# JLink-OB-Wiki.net
KiCad netlist of a schematic drawn in Altium Designer
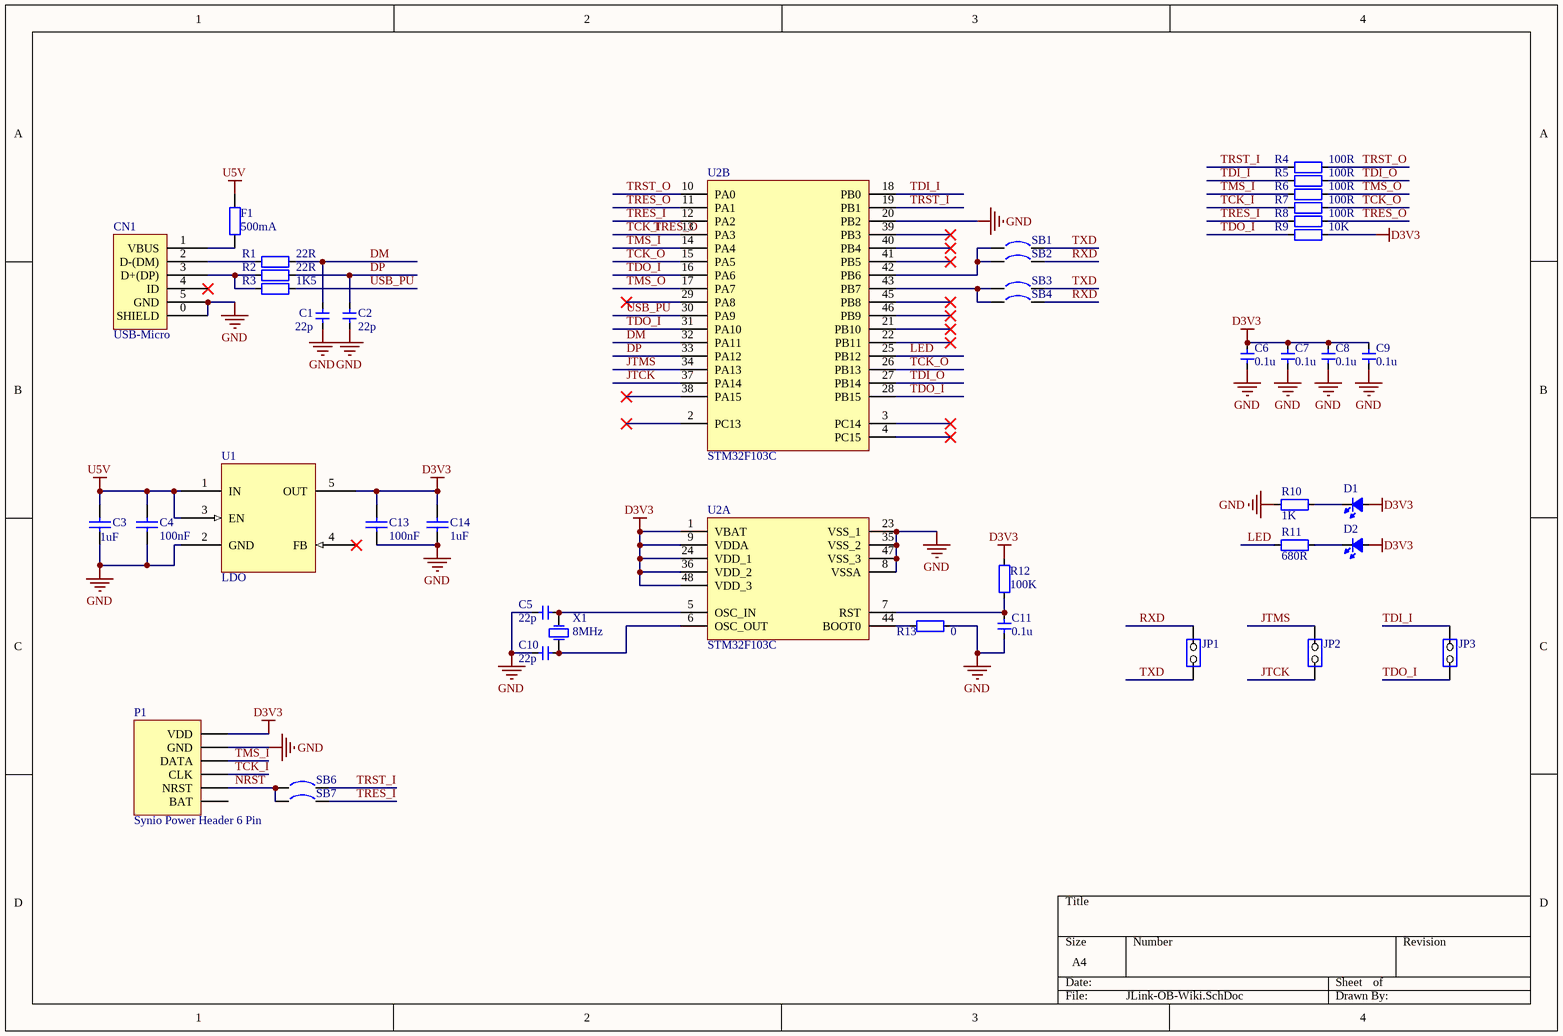
[diagram p0: JLink-OB-Wiki.SchDoc]

(export (version "E")
  (design (tool "Eeschema 10.0.6"))
  (components
    (comp (ref "C1")
      (value "22p")
      (footprint "0603C")
      (description "Capacitor")
      (fields (field (name "Comment") "Cap_0603"))
      (libsource (lib "altium-import") (part "root_1_Cap_0603_"))
    )
    (comp (ref "C2")
      (value "22p")
      (footprint "0603C")
      (description "Capacitor")
      (fields (field (name "Comment") "Cap_0603"))
      (libsource (lib "SCH_Passive") (part "Cap_0603"))
    )
    (comp (ref "C3")
      (value "1uF")
      (footprint "0603C")
      (description "0603  X5R 1礔")
      (fields (field (name "TOLERANCE") "10%"))
      (libsource (lib "MB963_1") (part "CAP SMD 0603  X5R 1礔 25V 10%"))
    )
    (comp (ref "C4")
      (value "100nF")
      (footprint "0603C")
      (description "Capacitor 0402 / 0603 / 0805")
      (libsource (lib "MCD_TOOLS") (part "Capacitor_ST"))
    )
    (comp (ref "C5")
      (value "22p")
      (footprint "0603C")
      (description "Capacitor")
      (fields (field (name "Comment") "Cap_0603"))
      (libsource (lib "SCH_Passive") (part "Cap_0603"))
    )
    (comp (ref "C6")
      (value "0.1u")
      (footprint "0603C")
      (description "Capacitor")
      (fields (field (name "Comment") "Cap_0603"))
      (libsource (lib "SCH_Passive") (part "Cap_0603"))
    )
    (comp (ref "C7")
      (value "0.1u")
      (footprint "0603C")
      (description "Capacitor")
      (fields (field (name "Comment") "Cap_0603"))
      (libsource (lib "SCH_Passive") (part "Cap_0603"))
    )
    (comp (ref "C8")
      (value "0.1u")
      (footprint "0603C")
      (description "Capacitor")
      (fields (field (name "Comment") "Cap_0603"))
      (libsource (lib "SCH_Passive") (part "Cap_0603"))
    )
    (comp (ref "C9")
      (value "0.1u")
      (footprint "0603C")
      (description "Capacitor")
      (fields (field (name "Comment") "Cap_0603"))
      (libsource (lib "SCH_Passive") (part "Cap_0603"))
    )
    (comp (ref "C10")
      (value "22p")
      (footprint "0603C")
      (description "Capacitor")
      (fields (field (name "Comment") "Cap_0603"))
      (libsource (lib "SCH_Passive") (part "Cap_0603"))
    )
    (comp (ref "C11")
      (value "0.1u")
      (footprint "0603C")
      (description "Capacitor")
      (fields (field (name "Comment") "Cap_0603"))
      (libsource (lib "SCH_Passive") (part "Cap_0603"))
    )
    (comp (ref "C13")
      (value "100nF")
      (footprint "0603C")
      (description "Capacitor 0402 / 0603 / 0805")
      (libsource (lib "MCD_TOOLS") (part "Capacitor_ST"))
    )
    (comp (ref "C14")
      (value "1uF")
      (footprint "0603C")
      (description "0603  X5R 1礔")
      (fields (field (name "TOLERANCE") "10%"))
      (libsource (lib "MB963_1") (part "CAP SMD 0603  X5R 1礔 25V 10%"))
    )
    (comp (ref "CN1")
      (value "USB-Micro")
      (footprint "USB_MICRO_5S_B")
      (libsource (lib "USB") (part "USB-Micro"))
    )
    (comp (ref "D1")
      (value "LED_0603")
      (footprint "LED-0603")
      (description "LED")
      (libsource (lib "SCH_Active") (part "LED_0603"))
    )
    (comp (ref "D2")
      (value "LED_0603")
      (footprint "LED-0603")
      (description "LED")
      (libsource (lib "SCH_Active") (part "LED_0603"))
    )
    (comp (ref "F1")
      (value "500mA")
      (footprint "0805M")
      (description "Resistor")
      (fields (field (name "PUBLISHER") "Altium Limited"))
      (libsource (lib "Misc") (part "Res"))
    )
    (comp (ref "JP1") (value "JP2") (footprint "HDR1X2/2.54mm") (libsource (lib "Connector") (part "JP2")))
    (comp (ref "JP2") (value "JP2") (footprint "HDR1X2/2.54mm") (libsource (lib "Connector") (part "JP2")))
    (comp (ref "JP3") (value "JP2") (footprint "HDR1X2/2.54mm") (libsource (lib "Connector") (part "JP2")))
    (comp (ref "P1")
      (value "Synio Power Header 6 Pin")
      (footprint "HDR1X6/2.54MM")
      (libsource (lib "Connector") (part "Synio Power Header 6 Pin"))
    )
    (comp (ref "R1")
      (value "22R")
      (footprint "0603R")
      (description "Resistor")
      (fields (field (name "Comment") "Res_0603"))
      (libsource (lib "SCH_Passive") (part "Res_0603"))
    )
    (comp (ref "R2")
      (value "22R")
      (footprint "0603R")
      (description "Resistor")
      (fields (field (name "Comment") "Res_0603"))
      (libsource (lib "SCH_Passive") (part "Res_0603"))
    )
    (comp (ref "R3")
      (value "1K5")
      (footprint "0603R")
      (description "Resistor")
      (fields (field (name "Comment") "Res_0603"))
      (libsource (lib "SCH_Passive") (part "Res_0603"))
    )
    (comp (ref "R4")
      (value "100R")
      (footprint "0603R")
      (description "Resistor")
      (fields (field (name "Comment") "Res_0603"))
      (libsource (lib "altium-import") (part "root_0_Res_0603_"))
    )
    (comp (ref "R5")
      (value "100R")
      (footprint "0603R")
      (description "Resistor")
      (fields (field (name "Comment") "Res_0603"))
      (libsource (lib "SCH_Passive") (part "Res_0603"))
    )
    (comp (ref "R6")
      (value "100R")
      (footprint "0603R")
      (description "Resistor")
      (fields (field (name "Comment") "Res_0603"))
      (libsource (lib "SCH_Passive") (part "Res_0603"))
    )
    (comp (ref "R7")
      (value "100R")
      (footprint "0603R")
      (description "Resistor")
      (fields (field (name "Comment") "Res_0603"))
      (libsource (lib "SCH_Passive") (part "Res_0603"))
    )
    (comp (ref "R8")
      (value "100R")
      (footprint "0603R")
      (description "Resistor")
      (fields (field (name "Comment") "Res_0603"))
      (libsource (lib "SCH_Passive") (part "Res_0603"))
    )
    (comp (ref "R9")
      (value "10K")
      (footprint "0603R")
      (description "Resistor")
      (fields (field (name "Comment") "Res_0603"))
      (libsource (lib "SCH_Passive") (part "Res_0603"))
    )
    (comp (ref "R10")
      (value "1K")
      (footprint "0603R")
      (description "Resistor")
      (fields (field (name "Comment") "Res_0603"))
      (libsource (lib "SCH_Passive") (part "Res_0603"))
    )
    (comp (ref "R11")
      (value "680R")
      (footprint "0603R")
      (description "Resistor")
      (fields (field (name "Comment") "Res_0603"))
      (libsource (lib "SCH_Passive") (part "Res_0603"))
    )
    (comp (ref "R12")
      (value "100K")
      (footprint "0603R")
      (description "Resistor")
      (fields (field (name "Comment") "Res_0603"))
      (libsource (lib "") (part "Res_0603_2"))
    )
    (comp (ref "R13")
      (value "0")
      (footprint "0603R")
      (description "Resistor")
      (fields (field (name "Comment") "Res_0603"))
      (libsource (lib "") (part "Res_0603_1"))
    )
    (comp (ref "SB1")
      (value "Circuit Breaker")
      (footprint "JP2_SMD")
      (fields (field (name "PUBLISHER") "Altium Limited"))
      (libsource (lib "Misc") (part "Circuit Breaker"))
    )
    (comp (ref "SB2")
      (value "Circuit Breaker")
      (footprint "JP2_SMD")
      (fields (field (name "PUBLISHER") "Altium Limited"))
      (libsource (lib "Misc") (part "Circuit Breaker"))
    )
    (comp (ref "SB3")
      (value "Circuit Breaker")
      (footprint "JP2_SMD")
      (fields (field (name "PUBLISHER") "Altium Limited"))
      (libsource (lib "Misc") (part "Circuit Breaker"))
    )
    (comp (ref "SB4")
      (value "Circuit Breaker")
      (footprint "JP2_SMD")
      (fields (field (name "PUBLISHER") "Altium Limited"))
      (libsource (lib "Misc") (part "Circuit Breaker"))
    )
    (comp (ref "SB6")
      (value "Circuit Breaker")
      (footprint "JP2_SMD")
      (fields (field (name "PUBLISHER") "Altium Limited"))
      (libsource (lib "Misc") (part "Circuit Breaker"))
    )
    (comp (ref "SB7")
      (value "Circuit Breaker")
      (footprint "JP2_SMD")
      (fields (field (name "PUBLISHER") "Altium Limited"))
      (libsource (lib "Misc") (part "Circuit Breaker"))
    )
    (comp (ref "U1")
      (value "LDO")
      (footprint "SOT23-5")
      (description "General LDO SOT23-5")
      (libsource (lib "Power") (part "LDO-SOT23-5"))
    )
    (comp (ref "U2")
      (value "STM32F103C")
      (footprint "LQFP48_N")
      (description "MCU")
      (libsource (lib "SCH_IC") (part "STM32F103C"))
    )
    (comp (ref "X1")
      (value "8MHz")
      (footprint "XTAL")
      (description "Crystal Oscillator")
      (fields (field (name "Comment") "XTAL_5032_2P"))
      (libsource (lib "SCH_Oscillator") (part "XTAL_5032_2P"))
    )
  )
  (nets
    (net (code "1") (name "/DM") (class "Default")
      (node (ref "C1") (pin "2") (pinfunction "2_2") (pintype "passive"))
      (node (ref "R1") (pin "2") (pinfunction "2_2") (pintype "passive"))
      (node (ref "U2") (pin "32") (pinfunction "PA11_32") (pintype "passive"))
    )
    (net (code "2") (name "/DP") (class "Default")
      (node (ref "C2") (pin "2") (pinfunction "2_2") (pintype "passive"))
      (node (ref "R2") (pin "2") (pinfunction "2_2") (pintype "passive"))
      (node (ref "U2") (pin "33") (pinfunction "PA12_33") (pintype "passive"))
    )
    (net (code "3") (name "/JTCK") (class "Default")
      (node (ref "JP2") (pin "1") (pinfunction "COMMON_1") (pintype "passive"))
      (node (ref "U2") (pin "37") (pinfunction "PA14_37") (pintype "passive"))
    )
    (net (code "4") (name "/JTMS") (class "Default")
      (node (ref "JP2") (pin "2") (pinfunction "NO_2") (pintype "passive"))
      (node (ref "U2") (pin "34") (pinfunction "PA13_34") (pintype "passive"))
    )
    (net (code "5") (name "/LED") (class "Default")
      (node (ref "R11") (pin "1") (pinfunction "1_1") (pintype "passive"))
      (node (ref "U2") (pin "25") (pinfunction "PB12_25") (pintype "passive"))
    )
    (net (code "6") (name "/NRST") (class "Default")
      (node (ref "P1") (pin "5") (pinfunction "NRST_5") (pintype "passive"))
      (node (ref "SB6") (pin "1") (pinfunction "1_1") (pintype "passive"))
      (node (ref "SB7") (pin "1") (pinfunction "1_1") (pintype "passive"))
    )
    (net (code "7") (name "/RXD") (class "Default")
      (node (ref "JP1") (pin "2") (pinfunction "NO_2") (pintype "passive"))
      (node (ref "SB2") (pin "2") (pinfunction "2_2") (pintype "passive"))
      (node (ref "SB4") (pin "2") (pinfunction "2_2") (pintype "passive"))
    )
    (net (code "8") (name "/TCK_I") (class "Default")
      (node (ref "P1") (pin "4") (pinfunction "CLK_4") (pintype "passive"))
      (node (ref "R7") (pin "1") (pinfunction "1_1") (pintype "passive"))
      (node (ref "R8") (pin "2") (pinfunction "2_2") (pintype "passive"))
      (node (ref "U2") (pin "11") (pinfunction "PA1_11") (pintype "passive"))
      (node (ref "U2") (pin "13") (pinfunction "PA3_13") (pintype "passive"))
    )
    (net (code "9") (name "/TCK_O") (class "Default")
      (node (ref "R7") (pin "2") (pinfunction "2_2") (pintype "passive"))
      (node (ref "U2") (pin "15") (pinfunction "PA5_15") (pintype "passive"))
      (node (ref "U2") (pin "26") (pinfunction "PB13_26") (pintype "passive"))
    )
    (net (code "10") (name "/TDI_I") (class "Default")
      (node (ref "JP3") (pin "2") (pinfunction "NO_2") (pintype "passive"))
      (node (ref "R5") (pin "1") (pinfunction "1_1") (pintype "passive"))
      (node (ref "U2") (pin "18") (pinfunction "PB0_18") (pintype "passive"))
    )
    (net (code "11") (name "/TDI_O") (class "Default")
      (node (ref "R5") (pin "2") (pinfunction "2_2") (pintype "passive"))
      (node (ref "U2") (pin "27") (pinfunction "PB14_27") (pintype "passive"))
    )
    (net (code "12") (name "/TDO_I") (class "Default")
      (node (ref "JP3") (pin "1") (pinfunction "COMMON_1") (pintype "passive"))
      (node (ref "R9") (pin "1") (pinfunction "1_1") (pintype "passive"))
      (node (ref "U2") (pin "16") (pinfunction "PA6_16") (pintype "passive"))
      (node (ref "U2") (pin "28") (pinfunction "PB15_28") (pintype "passive"))
      (node (ref "U2") (pin "31") (pinfunction "PA10_31") (pintype "passive"))
    )
    (net (code "13") (name "/TMS_I") (class "Default")
      (node (ref "P1") (pin "3") (pinfunction "DATA_3") (pintype "passive"))
      (node (ref "R6") (pin "1") (pinfunction "1_1") (pintype "passive"))
      (node (ref "U2") (pin "14") (pinfunction "PA4_14") (pintype "passive"))
    )
    (net (code "14") (name "/TMS_O") (class "Default")
      (node (ref "R6") (pin "2") (pinfunction "2_2") (pintype "passive"))
      (node (ref "U2") (pin "17") (pinfunction "PA7_17") (pintype "passive"))
    )
    (net (code "15") (name "/TRES_I") (class "Default")
      (node (ref "R8") (pin "1") (pinfunction "1_1") (pintype "passive"))
      (node (ref "SB7") (pin "2") (pinfunction "2_2") (pintype "passive"))
      (node (ref "U2") (pin "12") (pinfunction "PA2_12") (pintype "passive"))
    )
    (net (code "16") (name "/TRST_I") (class "Default")
      (node (ref "R4") (pin "1") (pinfunction "1_1") (pintype "passive"))
      (node (ref "SB6") (pin "2") (pinfunction "2_2") (pintype "passive"))
      (node (ref "U2") (pin "19") (pinfunction "PB1_19") (pintype "passive"))
    )
    (net (code "17") (name "/TRST_O") (class "Default")
      (node (ref "R4") (pin "2") (pinfunction "2_2") (pintype "passive"))
      (node (ref "U2") (pin "10") (pinfunction "PA0_10") (pintype "passive"))
    )
    (net (code "18") (name "/TXD") (class "Default")
      (node (ref "JP1") (pin "1") (pinfunction "COMMON_1") (pintype "passive"))
      (node (ref "SB1") (pin "2") (pinfunction "2_2") (pintype "passive"))
      (node (ref "SB3") (pin "2") (pinfunction "2_2") (pintype "passive"))
    )
    (net (code "19") (name "/USB_PU") (class "Default")
      (node (ref "R3") (pin "2") (pinfunction "2_2") (pintype "passive"))
      (node (ref "U2") (pin "30") (pinfunction "PA9_30") (pintype "passive"))
    )
    (net (code "20") (name "D3V3") (class "Default")
      (node (ref "C13") (pin "2") (pinfunction "2_2") (pintype "passive"))
      (node (ref "C14") (pin "1") (pinfunction "1_1") (pintype "passive"))
      (node (ref "C6") (pin "1") (pinfunction "1_1") (pintype "passive"))
      (node (ref "C7") (pin "1") (pinfunction "1_1") (pintype "passive"))
      (node (ref "C8") (pin "1") (pinfunction "1_1") (pintype "passive"))
      (node (ref "C9") (pin "1") (pinfunction "1_1") (pintype "passive"))
      (node (ref "D1") (pin "1") (pinfunction "A_1") (pintype "passive"))
      (node (ref "D2") (pin "1") (pinfunction "A_1") (pintype "passive"))
      (node (ref "P1") (pin "1") (pinfunction "VDD_1") (pintype "passive"))
      (node (ref "R12") (pin "2") (pinfunction "2_2") (pintype "passive"))
      (node (ref "R9") (pin "2") (pinfunction "2_2") (pintype "passive"))
      (node (ref "U1") (pin "5") (pinfunction "OUT_5") (pintype "power_in"))
      (node (ref "U2") (pin "1") (pinfunction "VBAT_1") (pintype "passive"))
      (node (ref "U2") (pin "24") (pinfunction "VDD_1_24") (pintype "passive"))
      (node (ref "U2") (pin "36") (pinfunction "VDD_2_36") (pintype "passive"))
      (node (ref "U2") (pin "48") (pinfunction "VDD_3_48") (pintype "passive"))
      (node (ref "U2") (pin "9") (pinfunction "VDDA_9") (pintype "passive"))
    )
    (net (code "21") (name "GND") (class "Default")
      (node (ref "C1") (pin "1") (pinfunction "1_1") (pintype "passive"))
      (node (ref "C10") (pin "2") (pinfunction "2_2") (pintype "passive"))
      (node (ref "C11") (pin "2") (pinfunction "2_2") (pintype "passive"))
      (node (ref "C13") (pin "1") (pinfunction "1_1") (pintype "passive"))
      (node (ref "C14") (pin "2") (pinfunction "2_2") (pintype "passive"))
      (node (ref "C2") (pin "1") (pinfunction "1_1") (pintype "passive"))
      (node (ref "C3") (pin "1") (pinfunction "1_1") (pintype "passive"))
      (node (ref "C4") (pin "1") (pinfunction "1_1") (pintype "passive"))
      (node (ref "C5") (pin "2") (pinfunction "2_2") (pintype "passive"))
      (node (ref "C6") (pin "2") (pinfunction "2_2") (pintype "passive"))
      (node (ref "C7") (pin "2") (pinfunction "2_2") (pintype "passive"))
      (node (ref "C8") (pin "2") (pinfunction "2_2") (pintype "passive"))
      (node (ref "C9") (pin "2") (pinfunction "2_2") (pintype "passive"))
      (node (ref "CN1") (pin "0") (pinfunction "SHIELD_0") (pintype "passive"))
      (node (ref "CN1") (pin "5") (pinfunction "GND_5") (pintype "passive"))
      (node (ref "P1") (pin "2") (pinfunction "GND_2") (pintype "passive"))
      (node (ref "R10") (pin "1") (pinfunction "1_1") (pintype "passive"))
      (node (ref "R13") (pin "1") (pinfunction "1_1") (pintype "passive"))
      (node (ref "U1") (pin "2") (pinfunction "GND_2") (pintype "power_in"))
      (node (ref "U2") (pin "20") (pinfunction "PB2_20") (pintype "passive"))
      (node (ref "U2") (pin "23") (pinfunction "VSS_1_23") (pintype "passive"))
      (node (ref "U2") (pin "35") (pinfunction "VSS_2_35") (pintype "passive"))
      (node (ref "U2") (pin "47") (pinfunction "VSS_3_47") (pintype "passive"))
      (node (ref "U2") (pin "8") (pinfunction "VSSA_8") (pintype "passive"))
    )
    (net (code "22") (name "Net-(CN1-D+(DP))") (class "Default")
      (node (ref "CN1") (pin "3") (pinfunction "D+(DP)_3") (pintype "passive"))
      (node (ref "R2") (pin "1") (pinfunction "1_1") (pintype "passive"))
      (node (ref "R3") (pin "1") (pinfunction "1_1") (pintype "passive"))
    )
    (net (code "23") (name "Net-(CN1-D-(DM))") (class "Default")
      (node (ref "CN1") (pin "2") (pinfunction "D-(DM)_2") (pintype "passive"))
      (node (ref "R1") (pin "1") (pinfunction "1_1") (pintype "passive"))
    )
    (net (code "24") (name "Net-(CN1-VBUS)") (class "Default")
      (node (ref "CN1") (pin "1") (pinfunction "VBUS_1") (pintype "passive"))
      (node (ref "F1") (pin "1") (pinfunction "1_1") (pintype "passive"))
    )
    (net (code "25") (name "Net-(D1-K)") (class "Default")
      (node (ref "D1") (pin "2") (pinfunction "K_2") (pintype "passive"))
      (node (ref "R10") (pin "2") (pinfunction "2_2") (pintype "passive"))
    )
    (net (code "26") (name "Net-(D2-K)") (class "Default")
      (node (ref "D2") (pin "2") (pinfunction "K_2") (pintype "passive"))
      (node (ref "R11") (pin "2") (pinfunction "2_2") (pintype "passive"))
    )
    (net (code "27") (name "Net-(U2A-BOOT0)") (class "Default")
      (node (ref "R13") (pin "2") (pinfunction "2_2") (pintype "passive"))
      (node (ref "U2") (pin "44") (pinfunction "BOOT0_44") (pintype "passive"))
    )
    (net (code "28") (name "Net-(U2A-OSC_IN)") (class "Default")
      (node (ref "C5") (pin "1") (pinfunction "1_1") (pintype "passive"))
      (node (ref "U2") (pin "5") (pinfunction "OSC_IN_5") (pintype "passive"))
      (node (ref "X1") (pin "2") (pinfunction "OSC2_2") (pintype "passive"))
    )
    (net (code "29") (name "Net-(U2A-OSC_OUT)") (class "Default")
      (node (ref "C10") (pin "1") (pinfunction "1_1") (pintype "passive"))
      (node (ref "U2") (pin "6") (pinfunction "OSC_OUT_6") (pintype "passive"))
      (node (ref "X1") (pin "1") (pinfunction "OSC1_1") (pintype "passive"))
    )
    (net (code "30") (name "Net-(U2A-RST)") (class "Default")
      (node (ref "C11") (pin "1") (pinfunction "1_1") (pintype "passive"))
      (node (ref "R12") (pin "1") (pinfunction "1_1") (pintype "passive"))
      (node (ref "U2") (pin "7") (pinfunction "RST_7") (pintype "passive"))
    )
    (net (code "31") (name "Net-(U2B-PB6)") (class "Default")
      (node (ref "SB1") (pin "1") (pinfunction "1_1") (pintype "passive"))
      (node (ref "SB2") (pin "1") (pinfunction "1_1") (pintype "passive"))
      (node (ref "U2") (pin "42") (pinfunction "PB6_42") (pintype "passive"))
    )
    (net (code "32") (name "Net-(U2B-PB7)") (class "Default")
      (node (ref "SB3") (pin "1") (pinfunction "1_1") (pintype "passive"))
      (node (ref "SB4") (pin "1") (pinfunction "1_1") (pintype "passive"))
      (node (ref "U2") (pin "43") (pinfunction "PB7_43") (pintype "passive"))
    )
    (net (code "33") (name "U5V") (class "Default")
      (node (ref "C3") (pin "2") (pinfunction "2_2") (pintype "passive"))
      (node (ref "C4") (pin "2") (pinfunction "2_2") (pintype "passive"))
      (node (ref "F1") (pin "2") (pinfunction "2_2") (pintype "passive"))
      (node (ref "U1") (pin "1") (pinfunction "IN_1") (pintype "power_in"))
      (node (ref "U1") (pin "3") (pinfunction "EN_3") (pintype "input"))
    )
    (net (code "34") (name "unconnected-(CN1-ID-Pad4)") (class "Default")
      (node (ref "CN1") (pin "4") (pinfunction "ID_4") (pintype "passive+no_connect"))
    )
    (net (code "35") (name "unconnected-(P1-BAT-Pad6)") (class "Default")
      (node (ref "P1") (pin "6") (pinfunction "BAT_6") (pintype "passive"))
    )
    (net (code "36") (name "unconnected-(U1-FB-Pad4)") (class "Default")
      (node (ref "U1") (pin "4") (pinfunction "FB_4") (pintype "input+no_connect"))
    )
    (net (code "37") (name "unconnected-(U2B-PA8-Pad29)") (class "Default")
      (node (ref "U2") (pin "29") (pinfunction "PA8_29") (pintype "passive+no_connect"))
    )
    (net (code "38") (name "unconnected-(U2B-PA15-Pad38)") (class "Default")
      (node (ref "U2") (pin "38") (pinfunction "PA15_38") (pintype "passive+no_connect"))
    )
    (net (code "39") (name "unconnected-(U2B-PB3-Pad39)") (class "Default")
      (node (ref "U2") (pin "39") (pinfunction "PB3_39") (pintype "passive+no_connect"))
    )
    (net (code "40") (name "unconnected-(U2B-PB4-Pad40)") (class "Default")
      (node (ref "U2") (pin "40") (pinfunction "PB4_40") (pintype "passive+no_connect"))
    )
    (net (code "41") (name "unconnected-(U2B-PB5-Pad41)") (class "Default")
      (node (ref "U2") (pin "41") (pinfunction "PB5_41") (pintype "passive+no_connect"))
    )
    (net (code "42") (name "unconnected-(U2B-PB8-Pad45)") (class "Default")
      (node (ref "U2") (pin "45") (pinfunction "PB8_45") (pintype "passive+no_connect"))
    )
    (net (code "43") (name "unconnected-(U2B-PB9-Pad46)") (class "Default")
      (node (ref "U2") (pin "46") (pinfunction "PB9_46") (pintype "passive+no_connect"))
    )
    (net (code "44") (name "unconnected-(U2B-PB10-Pad21)") (class "Default")
      (node (ref "U2") (pin "21") (pinfunction "PB10_21") (pintype "passive+no_connect"))
    )
    (net (code "45") (name "unconnected-(U2B-PB11-Pad22)") (class "Default")
      (node (ref "U2") (pin "22") (pinfunction "PB11_22") (pintype "passive+no_connect"))
    )
    (net (code "46") (name "unconnected-(U2B-PC13-Pad2)") (class "Default")
      (node (ref "U2") (pin "2") (pinfunction "PC13_2") (pintype "passive+no_connect"))
    )
    (net (code "47") (name "unconnected-(U2B-PC14-Pad3)") (class "Default")
      (node (ref "U2") (pin "3") (pinfunction "PC14_3") (pintype "passive+no_connect"))
    )
    (net (code "48") (name "unconnected-(U2B-PC15-Pad4)") (class "Default")
      (node (ref "U2") (pin "4") (pinfunction "PC15_4") (pintype "passive+no_connect"))
    )
  )
)
